# Drone.net
KiCad netlist of a schematic drawn in EAGLE
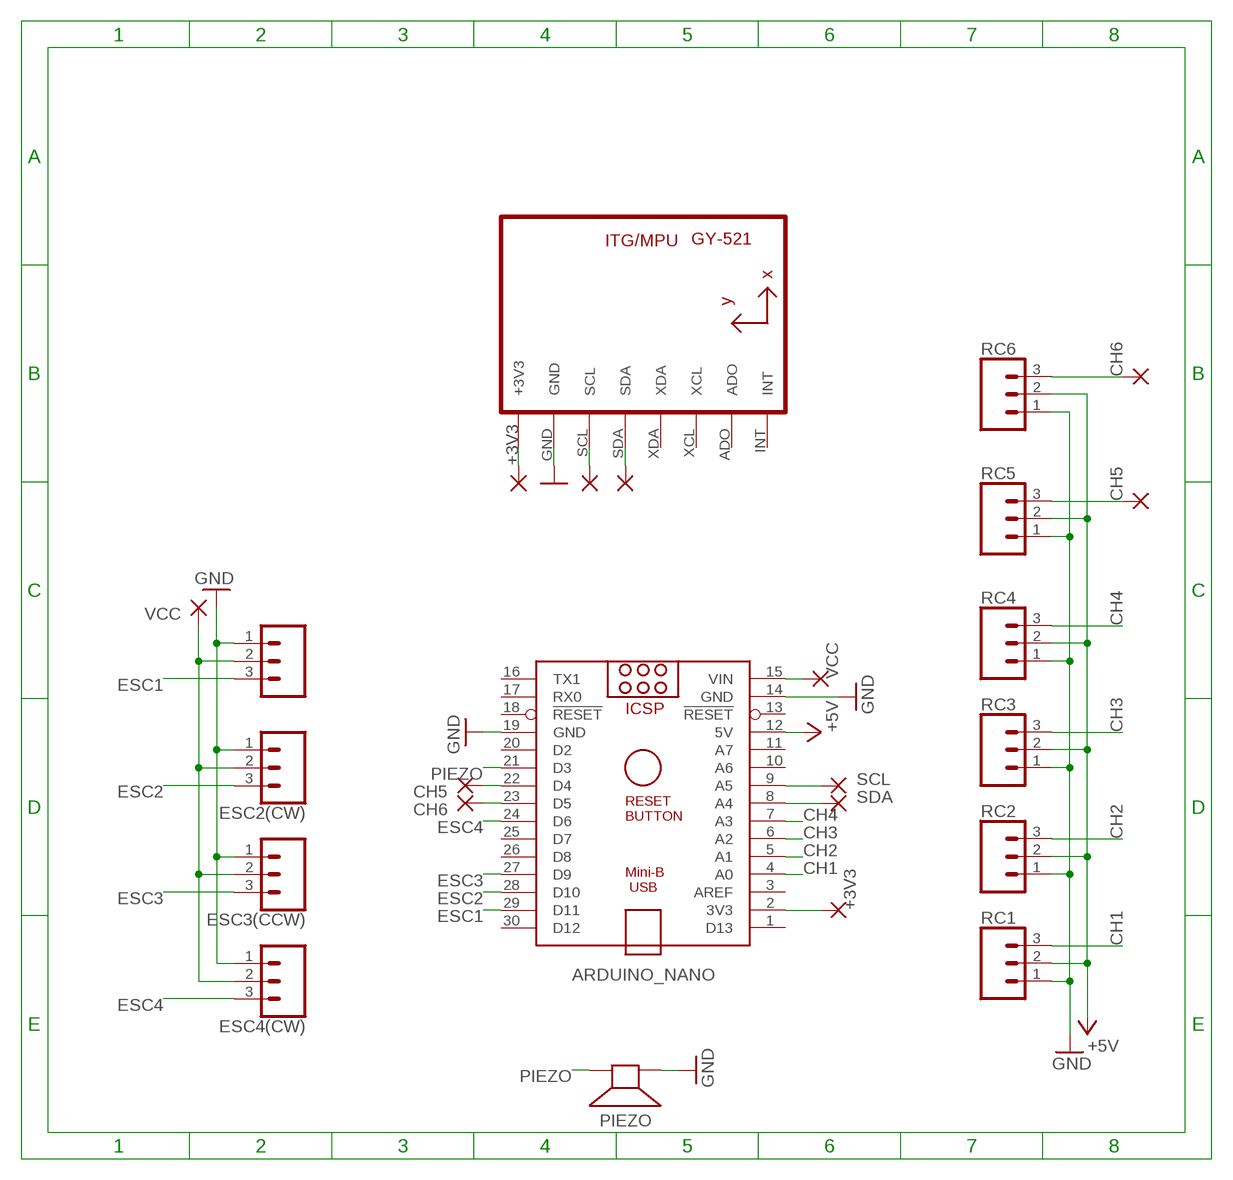
[diagram p0: schematic, sheet 1]

(export (version "E")
  (design (tool "Eeschema 10.0.6"))
  (components
    (comp (ref "+3V3-1")
      (value "+3V3")
      (footprint "eagle-import:1,6_0,8")
      (libsource (lib "eagle-import") (part "WIREPAD1,6/0,8"))
    )
    (comp (ref "+3V3-2")
      (value "+3V3")
      (footprint "eagle-import:1,6_0,8")
      (libsource (lib "eagle-import") (part "WIREPAD1,6/0,8"))
    )
    (comp (ref "ARDUINO_NANO")
      (value "ARDUINO_NANO")
      (footprint "eagle-import:ARDUINO_NANO")
      (libsource (lib "eagle-import") (part "ARDUINO_NANO"))
    )
    (comp (ref "CH5")
      (value "SCL")
      (footprint "eagle-import:1,6_0,8")
      (libsource (lib "eagle-import") (part "WIREPAD1,6/0,8"))
    )
    (comp (ref "CH5-2")
      (value "SCL")
      (footprint "eagle-import:1,6_0,8")
      (libsource (lib "eagle-import") (part "WIREPAD1,6/0,8"))
    )
    (comp (ref "CH6")
      (value "SCL")
      (footprint "eagle-import:1,6_0,8")
      (libsource (lib "eagle-import") (part "WIREPAD1,6/0,8"))
    )
    (comp (ref "CH6-2")
      (value "SCL")
      (footprint "eagle-import:1,6_0,8")
      (libsource (lib "eagle-import") (part "WIREPAD1,6/0,8"))
    )
    (comp (ref "ECS1(CCW)")
      (value "CONN_03")
      (footprint "eagle-import:1X03")
      (libsource (lib "eagle-import") (part "CONN_03"))
    )
    (comp (ref "ESC2(CW)")
      (value "CONN_03")
      (footprint "eagle-import:1X03")
      (libsource (lib "eagle-import") (part "CONN_03"))
    )
    (comp (ref "ESC3(CCW)")
      (value "CONN_03")
      (footprint "eagle-import:1X03")
      (libsource (lib "eagle-import") (part "CONN_03"))
    )
    (comp (ref "ESC4(CW)")
      (value "CONN_03")
      (footprint "eagle-import:1X03")
      (libsource (lib "eagle-import") (part "CONN_03"))
    )
    (comp (ref "PIEZO")
      (value "SPEAKER/AL60P")
      (footprint "eagle-import:AL60P")
      (libsource (lib "eagle-import") (part "SPEAKER/AL60P"))
    )
    (comp (ref "RC1")
      (value "CONN_03")
      (footprint "eagle-import:1X03")
      (libsource (lib "eagle-import") (part "CONN_03"))
    )
    (comp (ref "RC2")
      (value "CONN_03")
      (footprint "eagle-import:1X03")
      (libsource (lib "eagle-import") (part "CONN_03"))
    )
    (comp (ref "RC3")
      (value "CONN_03")
      (footprint "eagle-import:1X03")
      (libsource (lib "eagle-import") (part "CONN_03"))
    )
    (comp (ref "RC4")
      (value "CONN_03")
      (footprint "eagle-import:1X03")
      (libsource (lib "eagle-import") (part "CONN_03"))
    )
    (comp (ref "RC5")
      (value "CONN_03")
      (footprint "eagle-import:1X03")
      (libsource (lib "eagle-import") (part "CONN_03"))
    )
    (comp (ref "RC6")
      (value "CONN_03")
      (footprint "eagle-import:1X03")
      (libsource (lib "eagle-import") (part "CONN_03"))
    )
    (comp (ref "SCL")
      (value "SCL")
      (footprint "eagle-import:1,6_0,8")
      (libsource (lib "eagle-import") (part "WIREPAD1,6/0,8"))
    )
    (comp (ref "SCL-2")
      (value "SCL")
      (footprint "eagle-import:1,6_0,8")
      (libsource (lib "eagle-import") (part "WIREPAD1,6/0,8"))
    )
    (comp (ref "SDA")
      (value "SDA")
      (footprint "eagle-import:1,6_0,8")
      (libsource (lib "eagle-import") (part "WIREPAD1,6/0,8"))
    )
    (comp (ref "SDA-2")
      (value "SDA")
      (footprint "eagle-import:1,6_0,8")
      (libsource (lib "eagle-import") (part "WIREPAD1,6/0,8"))
    )
    (comp (ref "U1")
      (value "GY-521MPU6050")
      (footprint "eagle-import:GY-521")
      (libsource (lib "eagle-import") (part "GY-521MPU6050"))
    )
    (comp (ref "VCC-1")
      (value "VCC")
      (footprint "eagle-import:1,6_0,8")
      (libsource (lib "eagle-import") (part "WIREPAD1,6/0,8"))
    )
    (comp (ref "VCC-2")
      (value "VCC")
      (footprint "eagle-import:1,6_0,8")
      (libsource (lib "eagle-import") (part "WIREPAD1,6/0,8"))
    )
  )
  (nets
    (net (code "1") (name "+5V") (class "Default")
      (node (ref "ARDUINO_NANO") (pin "12") (pinfunction "5V_12") (pintype "power_in"))
      (node (ref "RC1") (pin "2") (pinfunction "2_2") (pintype "passive"))
      (node (ref "RC2") (pin "2") (pinfunction "2_2") (pintype "passive"))
      (node (ref "RC3") (pin "2") (pinfunction "2_2") (pintype "passive"))
      (node (ref "RC4") (pin "2") (pinfunction "2_2") (pintype "passive"))
      (node (ref "RC5") (pin "2") (pinfunction "2_2") (pintype "passive"))
      (node (ref "RC6") (pin "2") (pinfunction "2_2") (pintype "passive"))
    )
    (net (code "2") (name "/+3V3") (class "Default")
      (node (ref "+3V3-1") (pin "1") (pinfunction "P_1") (pintype "passive"))
      (node (ref "+3V3-2") (pin "1") (pinfunction "P_1") (pintype "passive"))
      (node (ref "ARDUINO_NANO") (pin "2") (pinfunction "3V3_2") (pintype "output"))
      (node (ref "U1") (pin "VCC") (pinfunction "+3V3_VCC") (pintype "bidirectional"))
    )
    (net (code "3") (name "/CH1") (class "Default")
      (node (ref "ARDUINO_NANO") (pin "4") (pinfunction "A0_4") (pintype "bidirectional"))
      (node (ref "RC1") (pin "3") (pinfunction "3_3") (pintype "passive"))
    )
    (net (code "4") (name "/CH2") (class "Default")
      (node (ref "ARDUINO_NANO") (pin "5") (pinfunction "A1_5") (pintype "bidirectional"))
      (node (ref "RC2") (pin "3") (pinfunction "3_3") (pintype "passive"))
    )
    (net (code "5") (name "/CH3") (class "Default")
      (node (ref "ARDUINO_NANO") (pin "6") (pinfunction "A2_6") (pintype "bidirectional"))
      (node (ref "RC3") (pin "3") (pinfunction "3_3") (pintype "passive"))
    )
    (net (code "6") (name "/CH4") (class "Default")
      (node (ref "ARDUINO_NANO") (pin "7") (pinfunction "A3_7") (pintype "bidirectional"))
      (node (ref "RC4") (pin "3") (pinfunction "3_3") (pintype "passive"))
    )
    (net (code "7") (name "/CH5") (class "Default")
      (node (ref "ARDUINO_NANO") (pin "22") (pinfunction "D4_22") (pintype "bidirectional"))
      (node (ref "CH5") (pin "1") (pinfunction "P_1") (pintype "passive"))
      (node (ref "CH5-2") (pin "1") (pinfunction "P_1") (pintype "passive"))
      (node (ref "RC5") (pin "3") (pinfunction "3_3") (pintype "passive"))
    )
    (net (code "8") (name "/CH6") (class "Default")
      (node (ref "ARDUINO_NANO") (pin "23") (pinfunction "D5_23") (pintype "bidirectional"))
      (node (ref "CH6") (pin "1") (pinfunction "P_1") (pintype "passive"))
      (node (ref "CH6-2") (pin "1") (pinfunction "P_1") (pintype "passive"))
      (node (ref "RC6") (pin "3") (pinfunction "3_3") (pintype "passive"))
    )
    (net (code "9") (name "/ESC1") (class "Default")
      (node (ref "ARDUINO_NANO") (pin "29") (pinfunction "D11_29") (pintype "bidirectional"))
      (node (ref "ECS1(CCW)") (pin "3") (pinfunction "3_3") (pintype "passive"))
    )
    (net (code "10") (name "/ESC2") (class "Default")
      (node (ref "ARDUINO_NANO") (pin "28") (pinfunction "D10_28") (pintype "bidirectional"))
      (node (ref "ESC2(CW)") (pin "3") (pinfunction "3_3") (pintype "passive"))
    )
    (net (code "11") (name "/ESC3") (class "Default")
      (node (ref "ARDUINO_NANO") (pin "27") (pinfunction "D9_27") (pintype "bidirectional"))
      (node (ref "ESC3(CCW)") (pin "3") (pinfunction "3_3") (pintype "passive"))
    )
    (net (code "12") (name "/ESC4") (class "Default")
      (node (ref "ARDUINO_NANO") (pin "24") (pinfunction "D6_24") (pintype "bidirectional"))
      (node (ref "ESC4(CW)") (pin "3") (pinfunction "3_3") (pintype "passive"))
    )
    (net (code "13") (name "/PIEZO") (class "Default")
      (node (ref "ARDUINO_NANO") (pin "21") (pinfunction "D3_21") (pintype "bidirectional"))
      (node (ref "PIEZO") (pin "2") (pinfunction "-_2") (pintype "passive"))
    )
    (net (code "14") (name "/SCL") (class "Default")
      (node (ref "ARDUINO_NANO") (pin "9") (pinfunction "A5_9") (pintype "bidirectional"))
      (node (ref "SCL") (pin "1") (pinfunction "P_1") (pintype "passive"))
      (node (ref "SCL-2") (pin "1") (pinfunction "P_1") (pintype "passive"))
      (node (ref "U1") (pin "SCL") (pinfunction "SCL_SCL") (pintype "bidirectional"))
    )
    (net (code "15") (name "/SDA") (class "Default")
      (node (ref "ARDUINO_NANO") (pin "8") (pinfunction "A4_8") (pintype "bidirectional"))
      (node (ref "SDA") (pin "1") (pinfunction "P_1") (pintype "passive"))
      (node (ref "SDA-2") (pin "1") (pinfunction "P_1") (pintype "passive"))
      (node (ref "U1") (pin "SDA") (pinfunction "SDA_SDA") (pintype "bidirectional"))
    )
    (net (code "16") (name "/VCC") (class "Default")
      (node (ref "ARDUINO_NANO") (pin "15") (pinfunction "VIN_15") (pintype "power_in"))
      (node (ref "ECS1(CCW)") (pin "2") (pinfunction "2_2") (pintype "passive"))
      (node (ref "ESC2(CW)") (pin "2") (pinfunction "2_2") (pintype "passive"))
      (node (ref "ESC3(CCW)") (pin "2") (pinfunction "2_2") (pintype "passive"))
      (node (ref "ESC4(CW)") (pin "2") (pinfunction "2_2") (pintype "passive"))
      (node (ref "VCC-1") (pin "1") (pinfunction "P_1") (pintype "passive"))
      (node (ref "VCC-2") (pin "1") (pinfunction "P_1") (pintype "passive"))
    )
    (net (code "17") (name "GND") (class "Default")
      (node (ref "ARDUINO_NANO") (pin "14") (pinfunction "GND_14") (pintype "power_in"))
      (node (ref "ARDUINO_NANO") (pin "19") (pinfunction "GND_19") (pintype "power_in"))
      (node (ref "ECS1(CCW)") (pin "1") (pinfunction "1_1") (pintype "passive"))
      (node (ref "ESC2(CW)") (pin "1") (pinfunction "1_1") (pintype "passive"))
      (node (ref "ESC3(CCW)") (pin "1") (pinfunction "1_1") (pintype "passive"))
      (node (ref "ESC4(CW)") (pin "1") (pinfunction "1_1") (pintype "passive"))
      (node (ref "PIEZO") (pin "1") (pinfunction "+_1") (pintype "passive"))
      (node (ref "RC1") (pin "1") (pinfunction "1_1") (pintype "passive"))
      (node (ref "RC2") (pin "1") (pinfunction "1_1") (pintype "passive"))
      (node (ref "RC3") (pin "1") (pinfunction "1_1") (pintype "passive"))
      (node (ref "RC4") (pin "1") (pinfunction "1_1") (pintype "passive"))
      (node (ref "RC5") (pin "1") (pinfunction "1_1") (pintype "passive"))
      (node (ref "RC6") (pin "1") (pinfunction "1_1") (pintype "passive"))
      (node (ref "U1") (pin "GND") (pinfunction "GND_GND") (pintype "bidirectional"))
    )
    (net (code "18") (name "unconnected-(ARDUINO_NANO-A6-Pad10)") (class "Default")
      (node (ref "ARDUINO_NANO") (pin "10") (pinfunction "A6_10") (pintype "bidirectional"))
    )
    (net (code "19") (name "unconnected-(ARDUINO_NANO-A7-Pad11)") (class "Default")
      (node (ref "ARDUINO_NANO") (pin "11") (pinfunction "A7_11") (pintype "bidirectional"))
    )
    (net (code "20") (name "unconnected-(ARDUINO_NANO-AREF-Pad3)") (class "Default")
      (node (ref "ARDUINO_NANO") (pin "3") (pinfunction "AREF_3") (pintype "input"))
    )
    (net (code "21") (name "unconnected-(ARDUINO_NANO-D2-Pad20)") (class "Default")
      (node (ref "ARDUINO_NANO") (pin "20") (pinfunction "D2_20") (pintype "bidirectional"))
    )
    (net (code "22") (name "unconnected-(ARDUINO_NANO-D7-Pad25)") (class "Default")
      (node (ref "ARDUINO_NANO") (pin "25") (pinfunction "D7_25") (pintype "bidirectional"))
    )
    (net (code "23") (name "unconnected-(ARDUINO_NANO-D8-Pad26)") (class "Default")
      (node (ref "ARDUINO_NANO") (pin "26") (pinfunction "D8_26") (pintype "bidirectional"))
    )
    (net (code "24") (name "unconnected-(ARDUINO_NANO-D12-Pad30)") (class "Default")
      (node (ref "ARDUINO_NANO") (pin "30") (pinfunction "D12_30") (pintype "bidirectional"))
    )
    (net (code "25") (name "unconnected-(ARDUINO_NANO-D13-Pad1)") (class "Default")
      (node (ref "ARDUINO_NANO") (pin "1") (pinfunction "D13_1") (pintype "bidirectional"))
    )
    (net (code "26") (name "unconnected-(ARDUINO_NANO-RX0-Pad17)") (class "Default")
      (node (ref "ARDUINO_NANO") (pin "17") (pinfunction "RX0_17") (pintype "bidirectional"))
    )
    (net (code "27") (name "unconnected-(ARDUINO_NANO-TX1-Pad16)") (class "Default")
      (node (ref "ARDUINO_NANO") (pin "16") (pinfunction "TX1_16") (pintype "bidirectional"))
    )
    (net (code "28") (name "unconnected-(ARDUINO_NANO-~{RESET}-Pad13)") (class "Default")
      (node (ref "ARDUINO_NANO") (pin "13") (pinfunction "~{RESET}_13") (pintype "input"))
    )
    (net (code "29") (name "unconnected-(ARDUINO_NANO-~{RESET}-Pad18)") (class "Default")
      (node (ref "ARDUINO_NANO") (pin "18") (pinfunction "~{RESET}_18") (pintype "input"))
    )
    (net (code "30") (name "unconnected-(U1-PadADO)") (class "Default")
      (node (ref "U1") (pin "ADO") (pinfunction "ADO_ADO") (pintype "bidirectional"))
    )
    (net (code "31") (name "unconnected-(U1-PadINT)") (class "Default")
      (node (ref "U1") (pin "INT") (pinfunction "INT_INT") (pintype "bidirectional"))
    )
    (net (code "32") (name "unconnected-(U1-PadXCL)") (class "Default")
      (node (ref "U1") (pin "XCL") (pinfunction "XCL_XCL") (pintype "bidirectional"))
    )
    (net (code "33") (name "unconnected-(U1-PadXDA)") (class "Default")
      (node (ref "U1") (pin "XDA") (pinfunction "XDA_XDA") (pintype "bidirectional"))
    )
  )
)
